# eletromiografia_PCB.net
KiCad netlist of a schematic drawn in EAGLE
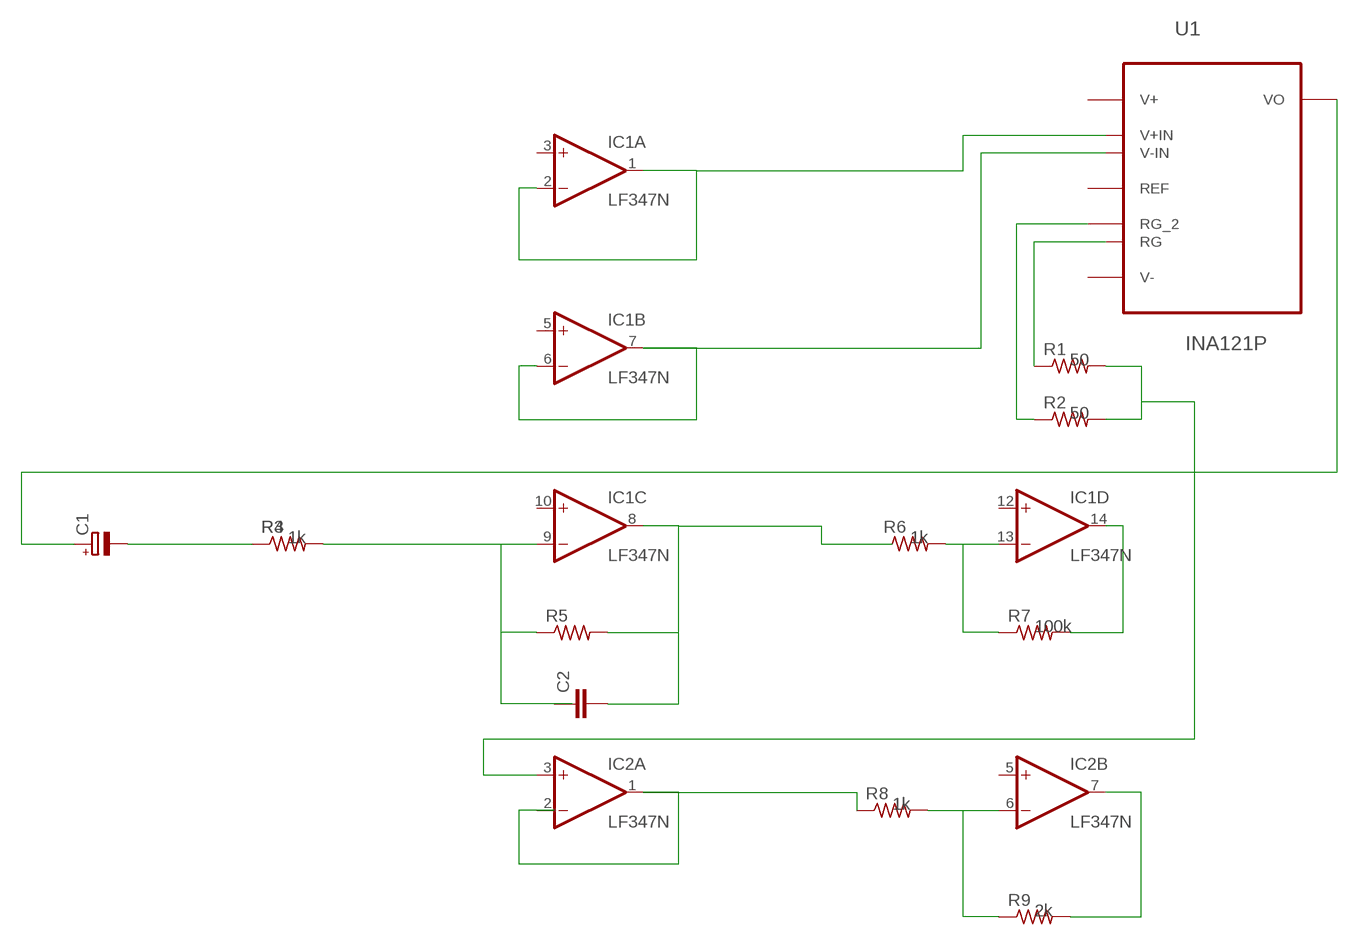
[diagram p0: schematic, sheet 1]

(export (version "E")
  (design (tool "Eeschema 10.0.6"))
  (components
    (comp (ref "C1")
      (value "CPOL-EUE5-13")
      (footprint "eagle-import:E5-13")
      (libsource (lib "eagle-import") (part "CPOL-EUE5-13"))
    )
    (comp (ref "C2")
      (value "C-EU050-030X075")
      (footprint "eagle-import:C050-030X075")
      (libsource (lib "eagle-import") (part "C-EU050-030X075"))
    )
    (comp (ref "IC1")
      (value "LF347N")
      (footprint "eagle-import:DIL14")
      (libsource (lib "eagle-import") (part "LF347N"))
    )
    (comp (ref "IC2")
      (value "LF347N")
      (footprint "eagle-import:DIL14")
      (libsource (lib "eagle-import") (part "LF347N"))
    )
    (comp (ref "R1")
      (value "R-US_0207/10")
      (footprint "eagle-import:0207_10")
      (fields (field (name "RG1") "50"))
      (libsource (lib "eagle-import") (part "R-US_0207/10"))
    )
    (comp (ref "R2")
      (value "R-US_0207/10")
      (footprint "eagle-import:0207_10")
      (fields (field (name "RG2") "50"))
      (libsource (lib "eagle-import") (part "R-US_0207/10"))
    )
    (comp (ref "R3")
      (value "R-US_0207/10")
      (footprint "eagle-import:0207_10")
      (libsource (lib "eagle-import") (part "R-US_0207/10"))
    )
    (comp (ref "R4")
      (value "R-US_0207/10")
      (footprint "eagle-import:0207_10")
      (fields (field (name "RC1") "1k"))
      (libsource (lib "eagle-import") (part "R-US_0207/10"))
    )
    (comp (ref "R5")
      (value "R-US_0207/10")
      (footprint "eagle-import:0207_10")
      (libsource (lib "eagle-import") (part "R-US_0207/10"))
    )
    (comp (ref "R6")
      (value "R-US_0207/10")
      (footprint "eagle-import:0207_10")
      (fields (field (name "R13") "1k"))
      (libsource (lib "eagle-import") (part "R-US_0207/10"))
    )
    (comp (ref "R7")
      (value "R-US_0207/10")
      (footprint "eagle-import:0207_10")
      (fields (field (name "R14") "100k"))
      (libsource (lib "eagle-import") (part "R-US_0207/10"))
    )
    (comp (ref "R8")
      (value "R-US_0207/10")
      (footprint "eagle-import:0207_10")
      (fields (field (name "R3") "1k"))
      (libsource (lib "eagle-import") (part "R-US_0207/10"))
    )
    (comp (ref "R9")
      (value "R-US_0207/10")
      (footprint "eagle-import:0207_10")
      (fields (field (name "R4") "2k"))
      (libsource (lib "eagle-import") (part "R-US_0207/10"))
    )
    (comp (ref "U1")
      (value "INA121P")
      (footprint "eagle-import:DIP254P762X508-8")
      (libsource (lib "eagle-import") (part "INA121P"))
    )
  )
  (nets
    (net (code "1") (name "/V+") (class "Default")
      (node (ref "U1") (pin "7") (pinfunction "V+_7") (pintype "power_in"))
    )
    (net (code "2") (name "/V-") (class "Default")
      (node (ref "U1") (pin "4") (pinfunction "V-_4") (pintype "power_in"))
    )
    (net (code "3") (name "Net-(C1-Pad-)") (class "Default")
      (node (ref "C1") (pin "-") (pinfunction "-_-") (pintype "passive"))
      (node (ref "R3") (pin "1") (pinfunction "1_1") (pintype "passive"))
      (node (ref "R4") (pin "1") (pinfunction "1_1") (pintype "passive"))
    )
    (net (code "4") (name "Net-(IC1A--IN)") (class "Default")
      (node (ref "IC1") (pin "1") (pinfunction "OUT_1") (pintype "output"))
      (node (ref "IC1") (pin "2") (pinfunction "-IN_2") (pintype "input"))
    )
    (net (code "5") (name "Net-(IC1B--IN)") (class "Default")
      (node (ref "IC1") (pin "6") (pinfunction "-IN_6") (pintype "input"))
      (node (ref "IC1") (pin "7") (pinfunction "OUT_7") (pintype "output"))
    )
    (net (code "6") (name "Net-(IC1C--IN)") (class "Default")
      (node (ref "IC1") (pin "9") (pinfunction "-IN_9") (pintype "input"))
      (node (ref "R3") (pin "2") (pinfunction "2_2") (pintype "passive"))
      (node (ref "R4") (pin "2") (pinfunction "2_2") (pintype "passive"))
      (node (ref "R5") (pin "1") (pinfunction "1_1") (pintype "passive"))
    )
    (net (code "7") (name "Net-(IC1C-OUT)") (class "Default")
      (node (ref "C2") (pin "2") (pinfunction "2_2") (pintype "passive"))
      (node (ref "IC1") (pin "8") (pinfunction "OUT_8") (pintype "output"))
      (node (ref "R5") (pin "2") (pinfunction "2_2") (pintype "passive"))
    )
    (net (code "8") (name "Net-(IC1D--IN)") (class "Default")
      (node (ref "IC1") (pin "13") (pinfunction "-IN_13") (pintype "input"))
      (node (ref "R6") (pin "2") (pinfunction "2_2") (pintype "passive"))
      (node (ref "R7") (pin "1") (pinfunction "1_1") (pintype "passive"))
    )
    (net (code "9") (name "Net-(IC1D-OUT)") (class "Default")
      (node (ref "IC1") (pin "14") (pinfunction "OUT_14") (pintype "output"))
      (node (ref "R7") (pin "2") (pinfunction "2_2") (pintype "passive"))
    )
    (net (code "10") (name "Net-(IC2A-+IN)") (class "Default")
      (node (ref "IC2") (pin "3") (pinfunction "+IN_3") (pintype "input"))
      (node (ref "R1") (pin "2") (pinfunction "2_2") (pintype "passive"))
      (node (ref "R2") (pin "2") (pinfunction "2_2") (pintype "passive"))
    )
    (net (code "11") (name "Net-(IC2A-OUT)") (class "Default")
      (node (ref "IC2") (pin "1") (pinfunction "OUT_1") (pintype "output"))
      (node (ref "R8") (pin "1") (pinfunction "1_1") (pintype "passive"))
    )
    (net (code "12") (name "Net-(IC2B--IN)") (class "Default")
      (node (ref "IC2") (pin "6") (pinfunction "-IN_6") (pintype "input"))
      (node (ref "R8") (pin "2") (pinfunction "2_2") (pintype "passive"))
      (node (ref "R9") (pin "1") (pinfunction "1_1") (pintype "passive"))
    )
    (net (code "13") (name "Net-(IC2B-OUT)") (class "Default")
      (node (ref "IC2") (pin "7") (pinfunction "OUT_7") (pintype "output"))
      (node (ref "R9") (pin "2") (pinfunction "2_2") (pintype "passive"))
    )
    (net (code "14") (name "Net-(U1-RG_2)") (class "Default")
      (node (ref "R2") (pin "1") (pinfunction "1_1") (pintype "passive"))
      (node (ref "U1") (pin "1") (pinfunction "RG_2_1") (pintype "passive"))
    )
    (net (code "15") (name "Net-(U1-VO)") (class "Default")
      (node (ref "C1") (pin "+") (pinfunction "+_+") (pintype "passive"))
      (node (ref "U1") (pin "6") (pinfunction "VO_6") (pintype "output"))
    )
    (net (code "16") (name "unconnected-(C2-Pad1)") (class "Default")
      (node (ref "C2") (pin "1") (pinfunction "1_1") (pintype "passive"))
    )
    (net (code "17") (name "unconnected-(IC1A-+IN-Pad3)") (class "Default")
      (node (ref "IC1") (pin "3") (pinfunction "+IN_3") (pintype "input"))
    )
    (net (code "18") (name "unconnected-(IC1B-+IN-Pad5)") (class "Default")
      (node (ref "IC1") (pin "5") (pinfunction "+IN_5") (pintype "input"))
    )
    (net (code "19") (name "unconnected-(IC1C-+IN-Pad10)") (class "Default")
      (node (ref "IC1") (pin "10") (pinfunction "+IN_10") (pintype "input"))
    )
    (net (code "20") (name "unconnected-(IC1D-+IN-Pad12)") (class "Default")
      (node (ref "IC1") (pin "12") (pinfunction "+IN_12") (pintype "input"))
    )
    (net (code "21") (name "unconnected-(IC2A--IN-Pad2)") (class "Default")
      (node (ref "IC2") (pin "2") (pinfunction "-IN_2") (pintype "input"))
    )
    (net (code "22") (name "unconnected-(IC2B-+IN-Pad5)") (class "Default")
      (node (ref "IC2") (pin "5") (pinfunction "+IN_5") (pintype "input"))
    )
    (net (code "23") (name "unconnected-(R1-Pad1)") (class "Default")
      (node (ref "R1") (pin "1") (pinfunction "1_1") (pintype "passive"))
    )
    (net (code "24") (name "unconnected-(R6-Pad1)") (class "Default")
      (node (ref "R6") (pin "1") (pinfunction "1_1") (pintype "passive"))
    )
    (net (code "25") (name "unconnected-(U1-REF-Pad5)") (class "Default")
      (node (ref "U1") (pin "5") (pinfunction "REF_5") (pintype "passive"))
    )
    (net (code "26") (name "unconnected-(U1-RG-Pad8)") (class "Default")
      (node (ref "U1") (pin "8") (pinfunction "RG_8") (pintype "passive"))
    )
    (net (code "27") (name "unconnected-(U1-V+IN-Pad3)") (class "Default")
      (node (ref "U1") (pin "3") (pinfunction "V+IN_3") (pintype "input"))
    )
    (net (code "28") (name "unconnected-(U1-V-IN-Pad2)") (class "Default")
      (node (ref "U1") (pin "2") (pinfunction "V-IN_2") (pintype "input"))
    )
  )
)
